# Input_Filter.net
KiCad netlist of a schematic drawn in Altium Designer
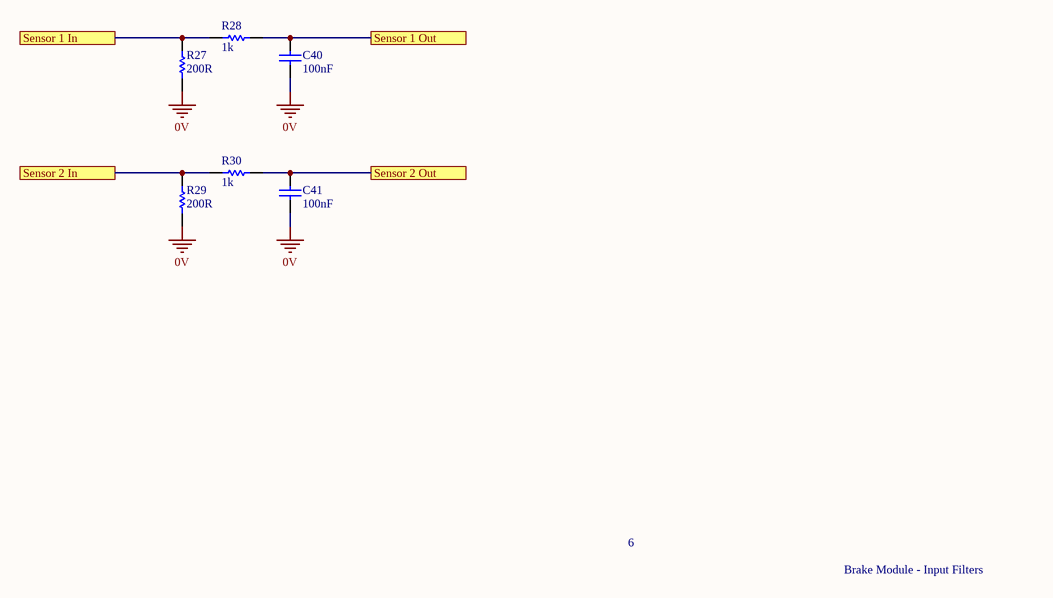
[diagram p0: Input Filter.SchDoc]

(export (version "E")
  (design (tool "Eeschema 10.0.6"))
  (components
    (comp (ref "C40")
      (value "100nF")
      (footprint "0805")
      (fields
        (field (name "PART NUMBER") "GCM21BR71H104KA37L")
        (field (name "TOLERANCE") "±10%")
        (field (name "MANUFACTURER") "muRata")
      )
      (libsource (lib "ts_20-standard-library") (part "Capacitor"))
    )
    (comp (ref "C41")
      (value "100nF")
      (footprint "0805")
      (fields
        (field (name "PART NUMBER") "GCM21BR71H104KA37L")
        (field (name "TOLERANCE") "±10%")
        (field (name "MANUFACTURER") "muRata")
      )
      (libsource (lib "ts_20-standard-library") (part "Capacitor"))
    )
    (comp (ref "R27")
      (value "200R")
      (footprint "0805")
      (fields
        (field (name "PART NUMBER") "RC0805FR07200RL")
        (field (name "MANUFACTURER") "YAGEO")
        (field (name "TOLERANCE") "0.01")
      )
      (libsource (lib "ts_20-standard-library") (part "Resistor"))
    )
    (comp (ref "R28")
      (value "1k")
      (footprint "0805")
      (fields
        (field (name "PART NUMBER") "RC0805FR071KL")
        (field (name "MANUFACTURER") "YAGEO")
        (field (name "TOLERANCE") "0.01")
      )
      (libsource (lib "ts_20-standard-library") (part "Resistor"))
    )
    (comp (ref "R29")
      (value "200R")
      (footprint "0805")
      (fields
        (field (name "PART NUMBER") "RC0805FR07200RL")
        (field (name "MANUFACTURER") "YAGEO")
        (field (name "TOLERANCE") "0.01")
      )
      (libsource (lib "ts_20-standard-library") (part "Resistor"))
    )
    (comp (ref "R30")
      (value "1k")
      (footprint "0805")
      (fields
        (field (name "PART NUMBER") "RC0805FR071KL")
        (field (name "MANUFACTURER") "YAGEO")
        (field (name "TOLERANCE") "0.01")
      )
      (libsource (lib "ts_20-standard-library") (part "Resistor"))
    )
  )
  (nets
    (net (code "1") (name "/Sensor 1 In") (class "Default")
      (node (ref "R27") (pin "2") (pinfunction "2_2") (pintype "passive"))
      (node (ref "R28") (pin "1") (pinfunction "1_1") (pintype "passive"))
    )
    (net (code "2") (name "/Sensor 1 Out") (class "Default")
      (node (ref "C40") (pin "2") (pinfunction "2_2") (pintype "passive"))
      (node (ref "R28") (pin "2") (pinfunction "2_2") (pintype "passive"))
    )
    (net (code "3") (name "/Sensor 2 In") (class "Default")
      (node (ref "R29") (pin "2") (pinfunction "2_2") (pintype "passive"))
      (node (ref "R30") (pin "1") (pinfunction "1_1") (pintype "passive"))
    )
    (net (code "4") (name "/Sensor 2 Out") (class "Default")
      (node (ref "C41") (pin "2") (pinfunction "2_2") (pintype "passive"))
      (node (ref "R30") (pin "2") (pinfunction "2_2") (pintype "passive"))
    )
    (net (code "5") (name "0V") (class "Default")
      (node (ref "C40") (pin "1") (pinfunction "1_1") (pintype "passive"))
      (node (ref "C41") (pin "1") (pinfunction "1_1") (pintype "passive"))
      (node (ref "R27") (pin "1") (pinfunction "1_1") (pintype "passive"))
      (node (ref "R29") (pin "1") (pinfunction "1_1") (pintype "passive"))
    )
  )
)
